# PowerSupply.net
KiCad netlist of a schematic drawn in Altium Designer
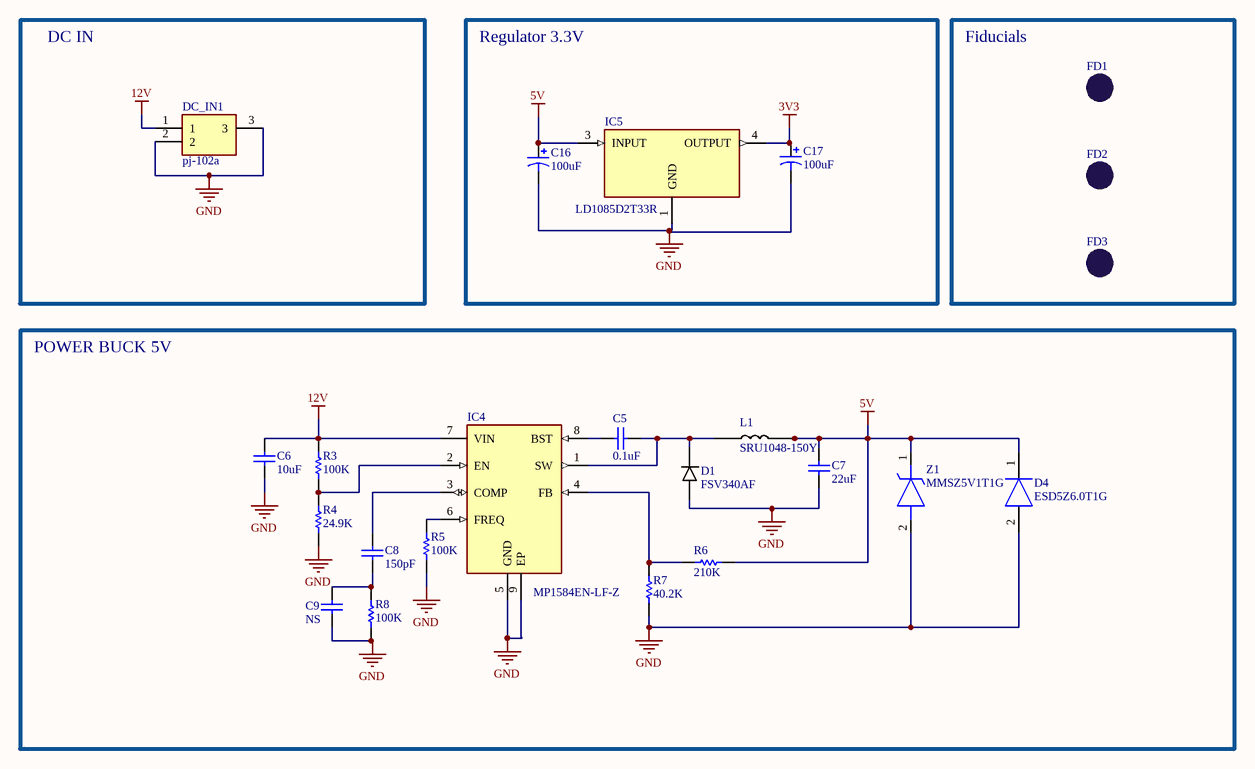
[diagram p0: PowerSupply.SchDoc]

(export (version "E")
  (design (tool "Eeschema 10.0.6"))
  (components
    (comp (ref "C5") (value "0.1uF") (footprint "C0603_N") (libsource (lib "General") (part "C_SMD")))
    (comp (ref "C6") (value "10uF") (footprint "C0805_N") (libsource (lib "General") (part "C_SMD")))
    (comp (ref "C7") (value "22uF") (footprint "C0805_N") (libsource (lib "General") (part "C_SMD")))
    (comp (ref "C8") (value "150pF") (footprint "C0603_N") (libsource (lib "General") (part "C_SMD")))
    (comp (ref "C9") (value "NS") (footprint "C0603_N") (libsource (lib "General") (part "C_SMD")))
    (comp (ref "C16")
      (value "100uF")
      (footprint "C_TANT_A_3216_N")
      (libsource (lib "General") (part "CP_SMD"))
    )
    (comp (ref "C17")
      (value "100uF")
      (footprint "C_TANT_A_3216_N")
      (libsource (lib "General") (part "CP_SMD"))
    )
    (comp (ref "D1")
      (value "FSV340AF")
      (footprint "SamacSys:SODFL4725X100N")
      (description "Diode")
      (fields (field (name "MOUSER PART NUMBER") "512-FSV340AF"))
      (libsource (lib "SamacSys") (part "FSV340AF"))
    )
    (comp (ref "D4")
      (value "ESD5Z6.0T1G")
      (footprint "SamacSys:SODFL1608X70N")
      (description "Diode")
      (fields (field (name "MOUSER PART NUMBER") "863-ESD5Z6.0T1G"))
      (libsource (lib "*") (part "ESD5Z6.0T1G"))
    )
    (comp (ref "DC_IN1")
      (value "pj-102a")
      (footprint "SamacSys:PJ059A")
      (description "Connector")
      (fields
        (field (name "MANUFACTURER_PART_NUMBER") "PJ-059A")
        (field (name "MOUSER PART NUMBER") "490-PJ-059A")
      )
      (libsource (lib "*") (part "PJ-059A"))
    )
    (comp (ref "FD1")
      (value "Fiducial")
      (footprint "Fiducial")
      (libsource (lib "SamacSys") (part "Fiducial"))
    )
    (comp (ref "FD2")
      (value "Fiducial")
      (footprint "Fiducial")
      (libsource (lib "SamacSys") (part "Fiducial"))
    )
    (comp (ref "FD3")
      (value "Fiducial")
      (footprint "Fiducial")
      (libsource (lib "SamacSys") (part "Fiducial"))
    )
    (comp (ref "IC4")
      (value "MP1584EN-LF-Z")
      (footprint "SamacSys:SOIC127P600X170-9N")
      (description "Integrated Circuit")
      (fields (field (name "MOUSER PART NUMBER") "946-MP1584ENLFZ"))
      (libsource (lib "*") (part "MP1584EN-LF-Z"))
    )
    (comp (ref "IC5")
      (value "LD1085D2T33R")
      (footprint "SamacSys:LD1085D2T33R")
      (description "Integrated Circuit")
      (fields
        (field (name "MOUSER PART NUMBER") "511-LD1085D2T33-TR")
        (field (name "RS PART NUMBER") "6869209P")
      )
      (libsource (lib "*") (part "LD1085D2T33R"))
    )
    (comp (ref "L1")
      (value "SRU1048-150Y")
      (footprint "SamacSys:SRU10486R8Y")
      (description "Inductor")
      (fields
        (field (name "MOUSER PART NUMBER") "652-SRU1048-150Y")
        (field (name "RS PART NUMBER") "7633590P")
      )
      (libsource (lib "SamacSys") (part "SRU1048-150Y"))
    )
    (comp (ref "R3")
      (value "100K")
      (footprint "R0603_N")
      (description "1%")
      (libsource (lib "General") (part "R_SMD"))
    )
    (comp (ref "R4")
      (value "24.9K")
      (footprint "R0603_N")
      (description "1%")
      (libsource (lib "General") (part "R_SMD"))
    )
    (comp (ref "R5")
      (value "100K")
      (footprint "R0603_N")
      (description "1%")
      (libsource (lib "General") (part "R_SMD"))
    )
    (comp (ref "R6")
      (value "210K")
      (footprint "R0603_N")
      (description "1%")
      (libsource (lib "General") (part "R_SMD"))
    )
    (comp (ref "R7")
      (value "40.2K")
      (footprint "R0603_N")
      (description "1%")
      (libsource (lib "General") (part "R_SMD"))
    )
    (comp (ref "R8")
      (value "100K")
      (footprint "R0603_N")
      (description "1%")
      (libsource (lib "General") (part "R_SMD"))
    )
    (comp (ref "Z1")
      (value "MMSZ5V1T1G")
      (footprint "SamacSys:SOD3716X135N")
      (description "Zener Diode")
      (fields (field (name "MOUSER PART NUMBER") "863-MMSZ5V1T1G"))
      (libsource (lib "*") (part "MMSZ5V1T1G"))
    )
  )
  (nets
    (net (code "1") (name "3V3") (class "Default")
      (node (ref "C17") (pin "1") (pinfunction "1_1") (pintype "passive"))
      (node (ref "IC5") (pin "4") (pinfunction "OUTPUT_4") (pintype "output"))
    )
    (net (code "2") (name "5V") (class "Default")
      (node (ref "C16") (pin "1") (pinfunction "1_1") (pintype "passive"))
      (node (ref "C7") (pin "1") (pinfunction "1_1") (pintype "passive"))
      (node (ref "D4") (pin "1") (pinfunction "K_1") (pintype "passive"))
      (node (ref "IC5") (pin "3") (pinfunction "INPUT_3") (pintype "input"))
      (node (ref "L1") (pin "2") (pinfunction "2_2") (pintype "passive"))
      (node (ref "R6") (pin "1") (pinfunction "1_1") (pintype "passive"))
      (node (ref "Z1") (pin "1") (pinfunction "K_1") (pintype "passive"))
    )
    (net (code "3") (name "12V") (class "Default")
      (node (ref "C6") (pin "2") (pinfunction "2_2") (pintype "passive"))
      (node (ref "DC_IN1") (pin "1") (pinfunction "1_1") (pintype "passive"))
      (node (ref "IC4") (pin "7") (pinfunction "VIN_7") (pintype "power_in"))
      (node (ref "R3") (pin "1") (pinfunction "1_1") (pintype "passive"))
    )
    (net (code "4") (name "GND") (class "Default")
      (node (ref "C16") (pin "2") (pinfunction "2_2") (pintype "passive"))
      (node (ref "C17") (pin "2") (pinfunction "2_2") (pintype "passive"))
      (node (ref "C6") (pin "1") (pinfunction "1_1") (pintype "passive"))
      (node (ref "C7") (pin "2") (pinfunction "2_2") (pintype "passive"))
      (node (ref "C9") (pin "1") (pinfunction "1_1") (pintype "passive"))
      (node (ref "D1") (pin "2") (pinfunction "A_2") (pintype "passive"))
      (node (ref "D4") (pin "2") (pinfunction "A_2") (pintype "passive"))
      (node (ref "DC_IN1") (pin "2") (pinfunction "2_2") (pintype "passive"))
      (node (ref "DC_IN1") (pin "3") (pinfunction "3_3") (pintype "passive"))
      (node (ref "IC4") (pin "5") (pinfunction "GND_5") (pintype "power_in"))
      (node (ref "IC4") (pin "9") (pinfunction "EP_9") (pintype "passive"))
      (node (ref "IC5") (pin "1") (pinfunction "GND_1") (pintype "power_in"))
      (node (ref "R4") (pin "2") (pinfunction "2_2") (pintype "passive"))
      (node (ref "R5") (pin "2") (pinfunction "2_2") (pintype "passive"))
      (node (ref "R7") (pin "1") (pinfunction "1_1") (pintype "passive"))
      (node (ref "R8") (pin "2") (pinfunction "2_2") (pintype "passive"))
      (node (ref "Z1") (pin "2") (pinfunction "A_2") (pintype "passive"))
    )
    (net (code "5") (name "Net-(C8-Pad1)") (class "Default")
      (node (ref "C8") (pin "1") (pinfunction "1_1") (pintype "passive"))
      (node (ref "C9") (pin "2") (pinfunction "2_2") (pintype "passive"))
      (node (ref "R8") (pin "1") (pinfunction "1_1") (pintype "passive"))
    )
    (net (code "6") (name "Net-(D1-K)") (class "Default")
      (node (ref "C5") (pin "1") (pinfunction "1_1") (pintype "passive"))
      (node (ref "D1") (pin "1") (pinfunction "K_1") (pintype "passive"))
      (node (ref "IC4") (pin "1") (pinfunction "SW_1") (pintype "output"))
      (node (ref "L1") (pin "1") (pinfunction "1_1") (pintype "passive"))
    )
    (net (code "7") (name "Net-(IC4-BST)") (class "Default")
      (node (ref "C5") (pin "2") (pinfunction "2_2") (pintype "passive"))
      (node (ref "IC4") (pin "8") (pinfunction "BST_8") (pintype "input"))
    )
    (net (code "8") (name "Net-(IC4-COMP)") (class "Default")
      (node (ref "C8") (pin "2") (pinfunction "2_2") (pintype "passive"))
      (node (ref "IC4") (pin "3") (pinfunction "COMP_3") (pintype "bidirectional"))
    )
    (net (code "9") (name "Net-(IC4-EN)") (class "Default")
      (node (ref "IC4") (pin "2") (pinfunction "EN_2") (pintype "input"))
      (node (ref "R3") (pin "2") (pinfunction "2_2") (pintype "passive"))
      (node (ref "R4") (pin "1") (pinfunction "1_1") (pintype "passive"))
    )
    (net (code "10") (name "Net-(IC4-FB)") (class "Default")
      (node (ref "IC4") (pin "4") (pinfunction "FB_4") (pintype "input"))
      (node (ref "R6") (pin "2") (pinfunction "2_2") (pintype "passive"))
      (node (ref "R7") (pin "2") (pinfunction "2_2") (pintype "passive"))
    )
    (net (code "11") (name "Net-(IC4-FREQ)") (class "Default")
      (node (ref "IC4") (pin "6") (pinfunction "FREQ_6") (pintype "input"))
      (node (ref "R5") (pin "1") (pinfunction "1_1") (pintype "passive"))
    )
  )
)
